# Sheet2.net
KiCad netlist of a schematic drawn in Altium Designer
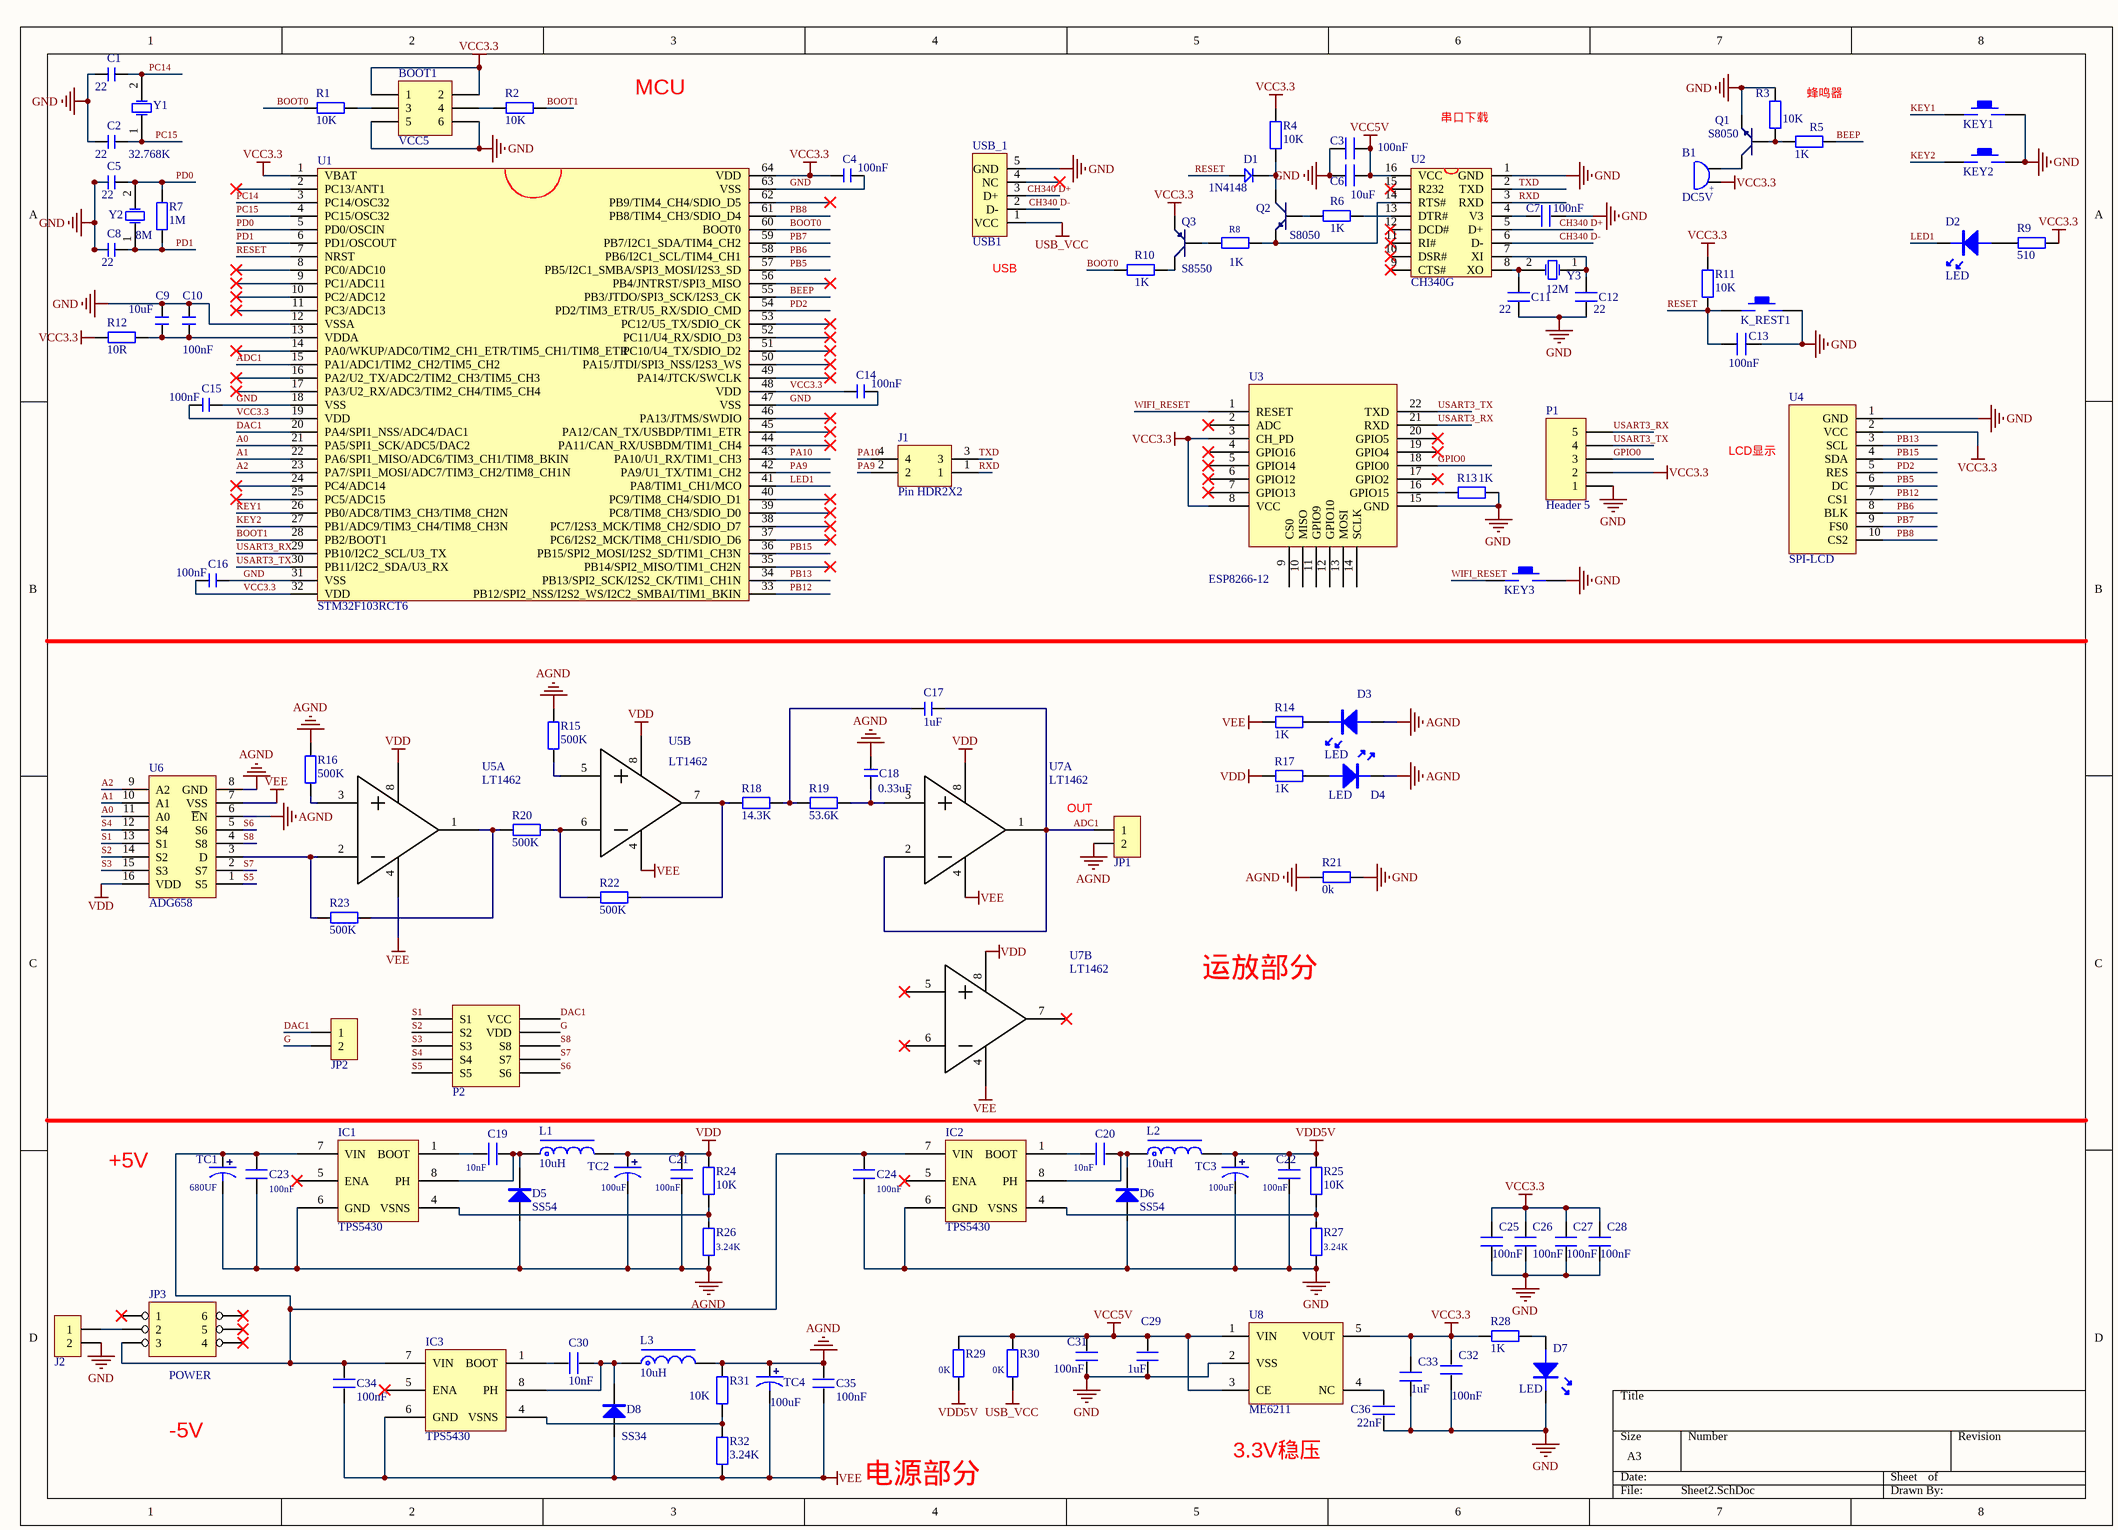
[diagram p0: Sheet2.SchDoc]

(export (version "E")
  (design (tool "Eeschema 10.0.6"))
  (components
    (comp (ref "B1")
      (value "DC5V")
      (footprint "BEEP 7.6x12x7.5")
      (description "蜂鸣器")
      (fields (field (name "版权归属") "源创客"))
      (libsource (lib "AD常用元器件集成库") (part "BEEP"))
    )
    (comp (ref "BOOT1")
      (value "VCC5")
      (footprint "HDR2X3")
      (description "Header, 3-Pin, Dual row")
      (fields (field (name "PUBLISHER") "Altium Limited"))
      (libsource (lib "SmartSensors") (part "Header 3X2"))
    )
    (comp (ref "C1")
      (value "22")
      (footprint "LC-0603_C")
      (description "无极性贴片电容")
      (fields (field (name "版权归属") "源创客"))
      (libsource (lib "SmartSensors") (part "C_1"))
    )
    (comp (ref "C2")
      (value "22")
      (footprint "LC-0603_C")
      (description "无极性贴片电容")
      (fields (field (name "版权归属") "源创客"))
      (libsource (lib "SmartSensors") (part "C_1"))
    )
    (comp (ref "C3") (value "100nF") (footprint "LC-0603_C") (libsource (lib "CORE") (part "C")))
    (comp (ref "C4")
      (value "100nF")
      (footprint "LC-0603_C")
      (description "无极性贴片电容")
      (fields (field (name "版权归属") "源创客"))
      (libsource (lib "SmartSensors") (part "C_1"))
    )
    (comp (ref "C5")
      (value "22")
      (footprint "LC-0603_C")
      (description "无极性贴片电容")
      (fields (field (name "版权归属") "源创客"))
      (libsource (lib "SmartSensors") (part "C_1"))
    )
    (comp (ref "C6") (value "10uF") (footprint "LC-0603_C") (libsource (lib "CORE") (part "C")))
    (comp (ref "C7") (value "100nF") (footprint "LC-0603_C") (libsource (lib "CORE") (part "C")))
    (comp (ref "C8")
      (value "22")
      (footprint "LC-0603_C")
      (description "无极性贴片电容")
      (fields (field (name "版权归属") "源创客"))
      (libsource (lib "SmartSensors") (part "C_1"))
    )
    (comp (ref "C9")
      (value "10uF")
      (footprint "LC-0603_C")
      (description "无极性贴片电容")
      (fields (field (name "版权归属") "源创客"))
      (libsource (lib "SmartSensors") (part "C_1"))
    )
    (comp (ref "C10")
      (value "100nF")
      (footprint "LC-0603_C")
      (description "无极性贴片电容")
      (fields (field (name "版权归属") "源创客"))
      (libsource (lib "SmartSensors") (part "C_1"))
    )
    (comp (ref "C11") (value "22") (footprint "LC-0603_C") (libsource (lib "CORE") (part "C")))
    (comp (ref "C12") (value "22") (footprint "LC-0603_C") (libsource (lib "CORE") (part "C")))
    (comp (ref "C13") (value "100nF") (footprint "LC-0603_C") (libsource (lib "CORE") (part "C")))
    (comp (ref "C14")
      (value "100nF")
      (footprint "LC-0603_C")
      (description "无极性贴片电容")
      (fields (field (name "版权归属") "源创客"))
      (libsource (lib "SmartSensors") (part "C_1"))
    )
    (comp (ref "C15")
      (value "100nF")
      (footprint "LC-0603_C")
      (description "无极性贴片电容")
      (fields (field (name "版权归属") "源创客"))
      (libsource (lib "SmartSensors") (part "C_1"))
    )
    (comp (ref "C16")
      (value "100nF")
      (footprint "LC-0603_C")
      (description "无极性贴片电容")
      (fields (field (name "版权归属") "源创客"))
      (libsource (lib "SmartSensors") (part "C_1"))
    )
    (comp (ref "C17")
      (value "1uF")
      (footprint "LC-0603_C")
      (description "无极性贴片电容")
      (fields (field (name "版权归属") "源创客"))
      (libsource (lib "AI电磁") (part "C"))
    )
    (comp (ref "C18")
      (value "0.33uF")
      (footprint "LC-0603_C")
      (description "无极性贴片电容")
      (fields (field (name "版权归属") "源创客"))
      (libsource (lib "AI电磁") (part "C"))
    )
    (comp (ref "C19") (value "10nF") (footprint "LC-0603_C") (libsource (lib "CORE") (part "C")))
    (comp (ref "C20") (value "10nF") (footprint "LC-0603_C") (libsource (lib "CORE") (part "C")))
    (comp (ref "C21") (value "100nF") (footprint "LC-0603_C") (libsource (lib "CORE") (part "C")))
    (comp (ref "C22") (value "100nF") (footprint "LC-0603_C") (libsource (lib "CORE") (part "C")))
    (comp (ref "C23") (value "100nF") (footprint "LC-0603_C") (libsource (lib "CORE") (part "C")))
    (comp (ref "C24") (value "100nF") (footprint "LC-0603_C") (libsource (lib "CORE") (part "C")))
    (comp (ref "C25") (value "100nF") (footprint "LC-0603_C") (libsource (lib "CORE") (part "C")))
    (comp (ref "C26") (value "100nF") (footprint "LC-0603_C") (libsource (lib "CORE") (part "C")))
    (comp (ref "C27") (value "100nF") (footprint "LC-0603_C") (libsource (lib "CORE") (part "C")))
    (comp (ref "C28") (value "100nF") (footprint "LC-0603_C") (libsource (lib "CORE") (part "C")))
    (comp (ref "C29") (value "1uF") (footprint "LC-0603_C") (libsource (lib "CORE") (part "C")))
    (comp (ref "C30") (value "10nF") (footprint "LC-0603_C") (libsource (lib "CORE") (part "C")))
    (comp (ref "C31") (value "100nF") (footprint "LC-0603_C") (libsource (lib "CORE") (part "C")))
    (comp (ref "C32") (value "100nF") (footprint "LC-0603_C") (libsource (lib "CORE") (part "C")))
    (comp (ref "C33") (value "1uF") (footprint "LC-0603_C") (libsource (lib "CORE") (part "C")))
    (comp (ref "C34") (value "100nF") (footprint "LC-0603_C") (libsource (lib "CORE") (part "C")))
    (comp (ref "C35") (value "100nF") (footprint "LC-0603_C") (libsource (lib "CORE") (part "C")))
    (comp (ref "C36") (value "22nF") (footprint "LC-0603_C") (libsource (lib "CORE") (part "C")))
    (comp (ref "D1") (value "1N4148") (footprint "DIODE_SOP") (libsource (lib "CORE") (part "D")))
    (comp (ref "D2") (value "LED") (footprint "LED-0805B") (libsource (lib "AI电磁") (part "LED")))
    (comp (ref "D3") (value "LED") (footprint "LED-0805B") (libsource (lib "AI电磁") (part "LED")))
    (comp (ref "D4") (value "LED") (footprint "LED-0805B") (libsource (lib "AI电磁") (part "LED")))
    (comp (ref "D5")
      (value "SS54")
      (footprint "LC-SMA(DO-214AC)_S2")
      (description "肖特基二极管")
      (fields (field (name "版权归属") "源创客"))
      (libsource (lib "AD常用元器件集成库") (part "SS54"))
    )
    (comp (ref "D6")
      (value "SS54")
      (footprint "LC-SMA(DO-214AC)_S2")
      (description "肖特基二极管")
      (fields (field (name "版权归属") "源创客"))
      (libsource (lib "AD常用元器件集成库") (part "SS54"))
    )
    (comp (ref "D7") (value "LED") (footprint "LED-0805B") (libsource (lib "AI电磁") (part "LED")))
    (comp (ref "D8")
      (value "SS34")
      (footprint "LC-SMA(DO-214AC)_S2")
      (description "肖特基二极管")
      (fields (field (name "版权归属") "源创客"))
      (libsource (lib "AD常用元器件集成库") (part "SS54"))
    )
    (comp (ref "IC1") (value "TPS5430") (footprint "SOP8") (libsource (lib "AD常用元器件集成库") (part "TPS5430")))
    (comp (ref "IC2") (value "TPS5430") (footprint "SOP8") (libsource (lib "AD常用元器件集成库") (part "TPS5430")))
    (comp (ref "IC3") (value "TPS5430") (footprint "SOP8") (libsource (lib "AD常用元器件集成库") (part "TPS5430")))
    (comp (ref "J1")
      (value "Pin HDR2X2")
      (footprint "Pin HDR2X2/2.54mm-S")
      (libsource (lib "SmartSensors") (part "Pin HDR2X2"))
    )
    (comp (ref "J2")
      (value "HDR-1X2")
      (footprint "XH2.54-2P")
      (description "2P接插件")
      (fields (field (name "版权归属") "源创客"))
      (libsource (lib "AI电磁") (part "Header 2_1"))
    )
    (comp (ref "JP1")
      (value "HDR-1X2")
      (footprint "HDR1X2")
      (description "2P接插件")
      (fields (field (name "版权归属") "源创客"))
      (libsource (lib "AI电磁") (part "Header 2"))
    )
    (comp (ref "JP2")
      (value "HDR-1X2")
      (footprint "HDR1X2")
      (description "2P接插件")
      (fields (field (name "版权归属") "源创客"))
      (libsource (lib "AI电磁") (part "Header 2"))
    )
    (comp (ref "JP3") (value "POWER") (footprint "6脚开关") (libsource (lib "AD常用元器件集成库") (part "6角开关")))
    (comp (ref "KEY1")
      (value "KEY_M")
      (footprint "DIP-6X6X5")
      (libsource (lib "SmartSensors") (part "KEY_M"))
    )
    (comp (ref "KEY2")
      (value "KEY_M")
      (footprint "DIP-6X6X5")
      (libsource (lib "SmartSensors") (part "KEY_M"))
    )
    (comp (ref "KEY3")
      (value "KEY_M")
      (footprint "SMD-3X6X2.5")
      (libsource (lib "SmartSensors") (part "KEY_M"))
    )
    (comp (ref "K_REST1")
      (value "KEY_M")
      (footprint "DIP-6X6X5")
      (libsource (lib "SmartSensors") (part "KEY_M"))
    )
    (comp (ref "L1")
      (value "10uH")
      (footprint "L-SMD-0630")
      (description "功率屏蔽电感")
      (fields (field (name "版权归属") "源创客"))
      (libsource (lib "AD常用元器件集成库") (part "L-CDRH"))
    )
    (comp (ref "L2")
      (value "10uH")
      (footprint "L-SMD-0630")
      (description "功率屏蔽电感")
      (fields (field (name "版权归属") "源创客"))
      (libsource (lib "AD常用元器件集成库") (part "L-CDRH"))
    )
    (comp (ref "L3")
      (value "10uH")
      (footprint "L-SMD-0630")
      (description "功率屏蔽电感")
      (fields (field (name "版权归属") "源创客"))
      (libsource (lib "AD常用元器件集成库") (part "L-CDRH"))
    )
    (comp (ref "P1")
      (value "Header 5")
      (footprint "HDR1X5")
      (description "Header, 5-Pin")
      (fields (field (name "PUBLISHER") "Altium Limited"))
      (libsource (lib "SmartSensors") (part "Header 5"))
    )
    (comp (ref "P2") (value "senor") (footprint "sensor-con pin 10") (libsource (lib "AI电磁") (part "senor")))
    (comp (ref "Q1")
      (value "S8050")
      (footprint "SOT-23R")
      (description "8050/BCW846/BCW847")
      (libsource (lib "CORE") (part "NPN"))
    )
    (comp (ref "Q2")
      (value "S8050")
      (footprint "SOT-23R")
      (description "8050/BCW846/BCW847")
      (libsource (lib "CORE") (part "NPN"))
    )
    (comp (ref "Q3")
      (value "S8550")
      (footprint "SOT-23R")
      (description "8550/BCW68")
      (libsource (lib "CORE") (part "PNP"))
    )
    (comp (ref "R1")
      (value "10K")
      (footprint "R 0603_M")
      (description "贴片电阻")
      (fields (field (name "版权归属") "源创客"))
      (libsource (lib "SmartSensors") (part "R"))
    )
    (comp (ref "R2")
      (value "10K")
      (footprint "R 0603_M")
      (description "贴片电阻")
      (fields (field (name "版权归属") "源创客"))
      (libsource (lib "SmartSensors") (part "R"))
    )
    (comp (ref "R3")
      (value "10K")
      (footprint "R 0603_M")
      (description "贴片电阻")
      (fields (field (name "版权归属") "源创客"))
      (libsource (lib "AD常用元器件集成库") (part "R"))
    )
    (comp (ref "R4")
      (value "10K")
      (footprint "R 0603_M")
      (description "贴片电阻")
      (fields (field (name "版权归属") "源创客"))
      (libsource (lib "AD常用元器件集成库") (part "R"))
    )
    (comp (ref "R5")
      (value "1K")
      (footprint "R 0603_M")
      (description "贴片电阻")
      (fields (field (name "版权归属") "源创客"))
      (libsource (lib "AD常用元器件集成库") (part "R"))
    )
    (comp (ref "R6")
      (value "1K")
      (footprint "R 0603_M")
      (description "贴片电阻")
      (fields (field (name "版权归属") "源创客"))
      (libsource (lib "AD常用元器件集成库") (part "R"))
    )
    (comp (ref "R7")
      (value "1M")
      (footprint "R 0603_M")
      (description "贴片电阻")
      (fields (field (name "版权归属") "源创客"))
      (libsource (lib "SmartSensors") (part "R"))
    )
    (comp (ref "R8")
      (value "1K")
      (footprint "R 0603_M")
      (description "贴片电阻")
      (fields (field (name "版权归属") "源创客"))
      (libsource (lib "AD常用元器件集成库") (part "R"))
    )
    (comp (ref "R9")
      (value "510")
      (footprint "R 0603_M")
      (description "贴片电阻")
      (fields (field (name "版权归属") "源创客"))
      (libsource (lib "AD常用元器件集成库") (part "R"))
    )
    (comp (ref "R10")
      (value "1K")
      (footprint "R 0603_M")
      (description "贴片电阻")
      (fields (field (name "版权归属") "源创客"))
      (libsource (lib "AD常用元器件集成库") (part "R"))
    )
    (comp (ref "R11")
      (value "10K")
      (footprint "R 0603_M")
      (description "贴片电阻")
      (fields (field (name "版权归属") "源创客"))
      (libsource (lib "AD常用元器件集成库") (part "R"))
    )
    (comp (ref "R12")
      (value "10R")
      (footprint "R 0603_M")
      (description "贴片电阻")
      (fields (field (name "版权归属") "源创客"))
      (libsource (lib "SmartSensors") (part "R"))
    )
    (comp (ref "R13")
      (value "1K")
      (footprint "R 0603_M")
      (description "贴片电阻")
      (fields (field (name "版权归属") "源创客"))
      (libsource (lib "AI电磁") (part "R"))
    )
    (comp (ref "R14")
      (value "1K")
      (footprint "R 0603_M")
      (description "贴片电阻")
      (fields (field (name "版权归属") "源创客"))
      (libsource (lib "AI电磁") (part "R"))
    )
    (comp (ref "R15")
      (value "500K")
      (footprint "R 0603_M")
      (description "贴片电阻")
      (fields (field (name "版权归属") "源创客"))
      (libsource (lib "AI电磁") (part "R"))
    )
    (comp (ref "R16")
      (value "500K")
      (footprint "R 0603_M")
      (description "贴片电阻")
      (fields (field (name "版权归属") "源创客"))
      (libsource (lib "AI电磁") (part "R"))
    )
    (comp (ref "R17")
      (value "1K")
      (footprint "R 0603_M")
      (description "贴片电阻")
      (fields (field (name "版权归属") "源创客"))
      (libsource (lib "AI电磁") (part "R"))
    )
    (comp (ref "R18")
      (value "14.3K")
      (footprint "R 0603_M")
      (description "贴片电阻")
      (fields (field (name "版权归属") "源创客"))
      (libsource (lib "AI电磁") (part "R"))
    )
    (comp (ref "R19")
      (value "53.6K")
      (footprint "R 0603_M")
      (description "贴片电阻")
      (fields (field (name "版权归属") "源创客"))
      (libsource (lib "AI电磁") (part "R"))
    )
    (comp (ref "R20")
      (value "500K")
      (footprint "R 0603_M")
      (description "贴片电阻")
      (fields (field (name "版权归属") "源创客"))
      (libsource (lib "AI电磁") (part "R"))
    )
    (comp (ref "R21")
      (value "0k")
      (footprint "R 0603_M")
      (description "贴片电阻")
      (fields (field (name "版权归属") "源创客"))
      (libsource (lib "AI电磁") (part "R"))
    )
    (comp (ref "R22")
      (value "500K")
      (footprint "R 0603_M")
      (description "贴片电阻")
      (fields (field (name "版权归属") "源创客"))
      (libsource (lib "AI电磁") (part "R"))
    )
    (comp (ref "R23")
      (value "500K")
      (footprint "R 0603_M")
      (description "贴片电阻")
      (fields (field (name "版权归属") "源创客"))
      (libsource (lib "AI电磁") (part "R"))
    )
    (comp (ref "R24")
      (value "10K")
      (footprint "R 0603_M")
      (description "贴片电阻")
      (fields (field (name "版权归属") "源创客"))
      (libsource (lib "AI电磁") (part "R"))
    )
    (comp (ref "R25")
      (value "10K")
      (footprint "R 0603_M")
      (description "贴片电阻")
      (fields (field (name "版权归属") "源创客"))
      (libsource (lib "AI电磁") (part "R"))
    )
    (comp (ref "R26")
      (value "3.24K")
      (footprint "R 0603_M")
      (description "贴片电阻")
      (fields (field (name "版权归属") "源创客"))
      (libsource (lib "AI电磁") (part "R"))
    )
    (comp (ref "R27")
      (value "3.24K")
      (footprint "R 0603_M")
      (description "贴片电阻")
      (fields (field (name "版权归属") "源创客"))
      (libsource (lib "AI电磁") (part "R"))
    )
    (comp (ref "R28")
      (value "1K")
      (footprint "R 0603_M")
      (description "贴片电阻")
      (fields (field (name "版权归属") "源创客"))
      (libsource (lib "AI电磁") (part "R"))
    )
    (comp (ref "R29")
      (value "0K")
      (footprint "R 0603_M")
      (description "贴片电阻")
      (fields (field (name "版权归属") "源创客"))
      (libsource (lib "AI电磁") (part "R"))
    )
    (comp (ref "R30")
      (value "0K")
      (footprint "R 0603_M")
      (description "贴片电阻")
      (fields (field (name "版权归属") "源创客"))
      (libsource (lib "AI电磁") (part "R"))
    )
    (comp (ref "R31")
      (value "10K")
      (footprint "R 0603_M")
      (description "贴片电阻")
      (fields (field (name "版权归属") "源创客"))
      (libsource (lib "AI电磁") (part "R"))
    )
    (comp (ref "R32")
      (value "3.24K")
      (footprint "R 0603_M")
      (description "贴片电阻")
      (fields (field (name "版权归属") "源创客"))
      (libsource (lib "AI电磁") (part "R"))
    )
    (comp (ref "TC1")
      (value "680UF")
      (footprint "SMD-EC6.3X6.3X10")
      (description "钽电容")
      (libsource (lib "AD常用元器件集成库") (part "TCAP_1"))
    )
    (comp (ref "TC2")
      (value "100uF")
      (footprint "TAJ-A/3216")
      (description "钽电容")
      (libsource (lib "AD常用元器件集成库") (part "TCAP_1"))
    )
    (comp (ref "TC3")
      (value "100uF")
      (footprint "TAJ-A/3216")
      (description "钽电容")
      (libsource (lib "AD常用元器件集成库") (part "TCAP_1"))
    )
    (comp (ref "TC4")
      (value "100uF")
      (footprint "TAJ-A/3216")
      (description "钽电容")
      (libsource (lib "AD常用元器件集成库") (part "TCAP_1"))
    )
    (comp (ref "U1")
      (value "STM32F103RCT6")
      (footprint "LQFP64")
      (libsource (lib "SmartSensors") (part "STM32F103RDT6"))
    )
    (comp (ref "U2")
      (value "CH340G")
      (footprint "SOP16M")
      (description "USB2UART")
      (libsource (lib "CORE") (part "CH340G"))
    )
    (comp (ref "U3")
      (value "ESP8266-12")
      (footprint "ESP8266-12")
      (libsource (lib "SmartSensors") (part "ESP8266-12"))
    )
    (comp (ref "U4")
      (value "SPI-LCD")
      (footprint "Fe-HDR1X10/2.54-S")
      (libsource (lib "SmartSensors") (part "SPI-LCD"))
    )
    (comp (ref "U5") (value "LT1462") (footprint "SOP8") (libsource (lib "AI电磁") (part "LT1462_1")))
    (comp (ref "U6") (value "ADG658") (footprint "ADG658-SOP-16") (libsource (lib "AI电磁") (part "ADG658")))
    (comp (ref "U7") (value "LT1462") (footprint "SOP8") (libsource (lib "AI电磁") (part "LT1462_1")))
    (comp (ref "U8") (value "ME6211") (footprint "SOT23-5") (libsource (lib "AD常用元器件集成库") (part "ME6211")))
    (comp (ref "USB_1") (value "USB1") (footprint "USB-micro_B") (libsource (lib "CORE") (part "USB5")))
    (comp (ref "Y1")
      (value "32.768K")
      (footprint "OSC 3215-2P")
      (description "Crystal Oscillator")
      (fields (field (name "PUBLISHER") "Altium Limited"))
      (libsource (lib "SmartSensors") (part "XTAL_2"))
    )
    (comp (ref "Y2")
      (value "8M")
      (footprint "OSC 5032-2P")
      (description "Crystal Oscillator")
      (fields (field (name "PUBLISHER") "Altium Limited"))
      (libsource (lib "SmartSensors") (part "XTAL_2"))
    )
    (comp (ref "Y3")
      (value "12M")
      (footprint "OSC 5032-2P")
      (description "Crystal Oscillator")
      (fields (field (name "PUBLISHER") "Altium Limited"))
      (libsource (lib "LD3320语音助手PCB_Project1") (part "XTAL_2"))
    )
  )
  (nets
    (net (code "1") (name "/A0") (class "Default")
      (node (ref "U1") (pin "21") (pinfunction "PA5/SPI1_SCK/ADC5/DAC2_21") (pintype "passive"))
      (node (ref "U6") (pin "11") (pinfunction "A0_11") (pintype "passive"))
    )
    (net (code "2") (name "/A1") (class "Default")
      (node (ref "U1") (pin "22") (pinfunction "PA6/SPI1_MISO/ADC6/TIM3_CH1/TIM8_BKIN_22") (pintype "passive"))
      (node (ref "U6") (pin "10") (pinfunction "A1_10") (pintype "passive"))
    )
    (net (code "3") (name "/A2") (class "Default")
      (node (ref "U1") (pin "23") (pinfunction "PA7/SPI1_MOSI/ADC7/TIM3_CH2/TIM8_CH1N_23") (pintype "passive"))
      (node (ref "U6") (pin "9") (pinfunction "A2_9") (pintype "passive"))
    )
    (net (code "4") (name "/ADC1") (class "Default")
      (node (ref "C17") (pin "2") (pinfunction "2_2") (pintype "passive"))
      (node (ref "JP1") (pin "1") (pinfunction "1_1") (pintype "passive"))
      (node (ref "U1") (pin "15") (pinfunction "PA1/ADC1/TIM2_CH2/TIM5_CH2_15") (pintype "passive"))
      (node (ref "U7") (pin "1") (pinfunction "out_1") (pintype "passive"))
      (node (ref "U7") (pin "2") (pinfunction "-_2") (pintype "passive"))
    )
    (net (code "5") (name "/BEEP") (class "Default")
      (node (ref "R5") (pin "2") (pinfunction "2_2") (pintype "passive"))
      (node (ref "U1") (pin "55") (pinfunction "PB3/JTDO/SPI3_SCK/I2S3_CK_55") (pintype "passive"))
    )
    (net (code "6") (name "/BOOT0") (class "Default")
      (node (ref "R1") (pin "1") (pinfunction "1_1") (pintype "passive"))
      (node (ref "R10") (pin "2") (pinfunction "2_2") (pintype "passive"))
      (node (ref "U1") (pin "60") (pinfunction "BOOT0_60") (pintype "passive"))
    )
    (net (code "7") (name "/BOOT1") (class "Default")
      (node (ref "R2") (pin "2") (pinfunction "2_2") (pintype "passive"))
      (node (ref "U1") (pin "28") (pinfunction "PB2/BOOT1_28") (pintype "passive"))
    )
    (net (code "8") (name "/CH340 D+") (class "Default")
      (node (ref "U2") (pin "5") (pinfunction "D+_5") (pintype "passive"))
      (node (ref "USB_1") (pin "3") (pinfunction "D+_3") (pintype "passive"))
    )
    (net (code "9") (name "/CH340 D-") (class "Default")
      (node (ref "U2") (pin "6") (pinfunction "D-_6") (pintype "passive"))
      (node (ref "USB_1") (pin "2") (pinfunction "D-_2") (pintype "passive"))
    )
    (net (code "10") (name "/DAC1") (class "Default")
      (node (ref "JP2") (pin "1") (pinfunction "1_1") (pintype "passive"))
      (node (ref "P2") (pin "10") (pinfunction "VCC_10") (pintype "passive"))
      (node (ref "U1") (pin "20") (pinfunction "PA4/SPI1_NSS/ADC4/DAC1_20") (pintype "passive"))
    )
    (net (code "11") (name "/G") (class "Default")
      (node (ref "JP2") (pin "2") (pinfunction "2_2") (pintype "passive"))
      (node (ref "P2") (pin "9") (pinfunction "VDD_9") (pintype "passive"))
    )
    (net (code "12") (name "/GPIO0") (class "Default")
      (node (ref "P1") (pin "3") (pinfunction "3_3") (pintype "passive"))
      (node (ref "U3") (pin "18") (pinfunction "GPIO0_18") (pintype "passive"))
    )
    (net (code "13") (name "/KEY1") (class "Default")
      (node (ref "KEY1") (pin "1") (pinfunction "1_1") (pintype "passive"))
      (node (ref "U1") (pin "26") (pinfunction "PB0/ADC8/TIM3_CH3/TIM8_CH2N_26") (pintype "passive"))
    )
    (net (code "14") (name "/KEY2") (class "Default")
      (node (ref "KEY2") (pin "1") (pinfunction "1_1") (pintype "passive"))
      (node (ref "U1") (pin "27") (pinfunction "PB1/ADC9/TIM3_CH4/TIM8_CH3N_27") (pintype "passive"))
    )
    (net (code "15") (name "/LED1") (class "Default")
      (node (ref "D2") (pin "K") (pinfunction "K_K") (pintype "passive"))
      (node (ref "U1") (pin "41") (pinfunction "PA8/TIM1_CH1/MCO_41") (pintype "passive"))
    )
    (net (code "16") (name "/PA9") (class "Default")
      (node (ref "J1") (pin "2") (pinfunction "2_2") (pintype "passive"))
      (node (ref "U1") (pin "42") (pinfunction "PA9/U1_TX/TIM1_CH2_42") (pintype "passive"))
    )
    (net (code "17") (name "/PA10") (class "Default")
      (node (ref "J1") (pin "4") (pinfunction "4_4") (pintype "passive"))
      (node (ref "U1") (pin "43") (pinfunction "PA10/U1_RX/TIM1_CH3_43") (pintype "passive"))
    )
    (net (code "18") (name "/PB5") (class "Default")
      (node (ref "U1") (pin "57") (pinfunction "PB5/I2C1_SMBA/SPI3_MOSI/I2S3_SD_57") (pintype "passive"))
      (node (ref "U4") (pin "6") (pinfunction "DC_6") (pintype "passive"))
    )
    (net (code "19") (name "/PB6") (class "Default")
      (node (ref "U1") (pin "58") (pinfunction "PB6/I2C1_SCL/TIM4_CH1_58") (pintype "passive"))
      (node (ref "U4") (pin "8") (pinfunction "BLK_8") (pintype "passive"))
    )
    (net (code "20") (name "/PB7") (class "Default")
      (node (ref "U1") (pin "59") (pinfunction "PB7/I2C1_SDA/TIM4_CH2_59") (pintype "passive"))
      (node (ref "U4") (pin "9") (pinfunction "FS0_9") (pintype "passive"))
    )
    (net (code "21") (name "/PB8") (class "Default")
      (node (ref "U1") (pin "61") (pinfunction "PB8/TIM4_CH3/SDIO_D4_61") (pintype "passive"))
      (node (ref "U4") (pin "10") (pinfunction "CS2_10") (pintype "passive"))
    )
    (net (code "22") (name "/PB12") (class "Default")
      (node (ref "U1") (pin "33") (pinfunction "PB12/SPI2_NSS/I2S2_WS/I2C2_SMBAI/TIM1_BKIN_33") (pintype "passive"))
      (node (ref "U4") (pin "7") (pinfunction "CS1_7") (pintype "passive"))
    )
    (net (code "23") (name "/PB13") (class "Default")
      (node (ref "U1") (pin "34") (pinfunction "PB13/SPI2_SCK/I2S2_CK/TIM1_CH1N_34") (pintype "passive"))
      (node (ref "U4") (pin "3") (pinfunction "SCL_3") (pintype "passive"))
    )
    (net (code "24") (name "/PB15") (class "Default")
      (node (ref "U1") (pin "36") (pinfunction "PB15/SPI2_MOSI/I2S2_SD/TIM1_CH3N_36") (pintype "passive"))
      (node (ref "U4") (pin "4") (pinfunction "SDA_4") (pintype "passive"))
    )
    (net (code "25") (name "/PC14") (class "Default")
      (node (ref "C1") (pin "2") (pinfunction "2_2") (pintype "passive"))
      (node (ref "U1") (pin "3") (pinfunction "PC14/OSC32_3") (pintype "passive"))
      (node (ref "Y1") (pin "2") (pinfunction "OSC2_2") (pintype "passive"))
    )
    (net (code "26") (name "/PC15") (class "Default")
      (node (ref "C2") (pin "2") (pinfunction "2_2") (pintype "passive"))
      (node (ref "U1") (pin "4") (pinfunction "PC15/OSC32_4") (pintype "passive"))
      (node (ref "Y1") (pin "1") (pinfunction "OSC1_1") (pintype "passive"))
    )
    (net (code "27") (name "/PD0") (class "Default")
      (node (ref "C5") (pin "2") (pinfunction "2_2") (pintype "passive"))
      (node (ref "R7") (pin "2") (pinfunction "2_2") (pintype "passive"))
      (node (ref "U1") (pin "5") (pinfunction "PD0/OSCIN_5") (pintype "passive"))
      (node (ref "Y2") (pin "2") (pinfunction "OSC2_2") (pintype "passive"))
    )
    (net (code "28") (name "/PD1") (class "Default")
      (node (ref "C8") (pin "2") (pinfunction "2_2") (pintype "passive"))
      (node (ref "R7") (pin "1") (pinfunction "1_1") (pintype "passive"))
      (node (ref "U1") (pin "6") (pinfunction "PD1/OSCOUT_6") (pintype "passive"))
      (node (ref "Y2") (pin "1") (pinfunction "OSC1_1") (pintype "passive"))
    )
    (net (code "29") (name "/PD2") (class "Default")
      (node (ref "U1") (pin "54") (pinfunction "PD2/TIM3_ETR/U5_RX/SDIO_CMD_54") (pintype "passive"))
      (node (ref "U4") (pin "5") (pinfunction "RES_5") (pintype "passive"))
    )
    (net (code "30") (name "/RESET") (class "Default")
      (node (ref "C13") (pin "2") (pintype "passive"))
      (node (ref "D1") (pin "1") (pintype "passive"))
      (node (ref "K_REST1") (pin "1") (pinfunction "1_1") (pintype "passive"))
      (node (ref "R11") (pin "1") (pinfunction "1_1") (pintype "passive"))
      (node (ref "U1") (pin "7") (pinfunction "NRST_7") (pintype "passive"))
    )
    (net (code "31") (name "/RXD") (class "Default")
      (node (ref "J1") (pin "1") (pinfunction "1_1") (pintype "passive"))
      (node (ref "U2") (pin "3") (pinfunction "RXD_3") (pintype "passive"))
    )
    (net (code "32") (name "/S1") (class "Default")
      (node (ref "P2") (pin "1") (pinfunction "S1_1") (pintype "passive"))
      (node (ref "U6") (pin "13") (pinfunction "S1_13") (pintype "passive"))
    )
    (net (code "33") (name "/S2") (class "Default")
      (node (ref "P2") (pin "2") (pinfunction "S2_2") (pintype "passive"))
      (node (ref "U6") (pin "14") (pinfunction "S2_14") (pintype "passive"))
    )
    (net (code "34") (name "/S3") (class "Default")
      (node (ref "P2") (pin "3") (pinfunction "S3_3") (pintype "passive"))
      (node (ref "U6") (pin "15") (pinfunction "S3_15") (pintype "passive"))
    )
    (net (code "35") (name "/S4") (class "Default")
      (node (ref "P2") (pin "4") (pinfunction "S4_4") (pintype "passive"))
      (node (ref "U6") (pin "12") (pinfunction "S4_12") (pintype "passive"))
    )
    (net (code "36") (name "/S5") (class "Default")
      (node (ref "P2") (pin "5") (pinfunction "S5_5") (pintype "passive"))
      (node (ref "U6") (pin "1") (pinfunction "S5_1") (pintype "passive"))
    )
    (net (code "37") (name "/S6") (class "Default")
      (node (ref "P2") (pin "6") (pinfunction "S6_6") (pintype "passive"))
      (node (ref "U6") (pin "5") (pinfunction "S6_5") (pintype "passive"))
    )
    (net (code "38") (name "/S7") (class "Default")
      (node (ref "P2") (pin "7") (pinfunction "S7_7") (pintype "passive"))
      (node (ref "U6") (pin "2") (pinfunction "S7_2") (pintype "passive"))
    )
    (net (code "39") (name "/S8") (class "Default")
      (node (ref "P2") (pin "8") (pinfunction "S8_8") (pintype "passive"))
      (node (ref "U6") (pin "4") (pinfunction "S8_4") (pintype "passive"))
    )
    (net (code "40") (name "/TXD") (class "Default")
      (node (ref "J1") (pin "3") (pinfunction "3_3") (pintype "passive"))
      (node (ref "U2") (pin "2") (pinfunction "TXD_2") (pintype "passive"))
    )
    (net (code "41") (name "/USART3_RX") (class "Default")
      (node (ref "P1") (pin "5") (pinfunction "5_5") (pintype "passive"))
      (node (ref "U1") (pin "29") (pinfunction "PB10/I2C2_SCL/U3_TX_29") (pintype "passive"))
      (node (ref "U3") (pin "21") (pinfunction "RXD_21") (pintype "passive"))
    )
    (net (code "42") (name "/USART3_TX") (class "Default")
      (node (ref "P1") (pin "4") (pinfunction "4_4") (pintype "passive"))
      (node (ref "U1") (pin "30") (pinfunction "PB11/I2C2_SDA/U3_RX_30") (pintype "passive"))
      (node (ref "U3") (pin "22") (pinfunction "TXD_22") (pintype "passive"))
    )
    (net (code "43") (name "/WIFI_RESET") (class "Default")
      (node (ref "KEY3") (pin "1") (pinfunction "1_1") (pintype "passive"))
      (node (ref "U3") (pin "1") (pinfunction "RESET_1") (pintype "passive"))
    )
    (net (code "44") (name "AGND") (class "Default")
      (node (ref "C18") (pin "1") (pinfunction "1_1") (pintype "passive"))
      (node (ref "C21") (pin "2") (pintype "passive"))
      (node (ref "C23") (pin "1") (pintype "passive"))
      (node (ref "C35") (pin "1") (pintype "passive"))
      (node (ref "D3") (pin "A") (pinfunction "A_A") (pintype "passive"))
      (node (ref "D4") (pin "K") (pinfunction "K_K") (pintype "passive"))
      (node (ref "D5") (pin "1") (pinfunction "A_1") (pintype "passive"))
      (node (ref "IC1") (pin "6") (pinfunction "GND_6") (pintype "passive"))
      (node (ref "JP1") (pin "2") (pinfunction "2_2") (pintype "passive"))
      (node (ref "L3") (pin "2") (pinfunction "2_2") (pintype "passive"))
      (node (ref "R15") (pin "1") (pinfunction "1_1") (pintype "passive"))
      (node (ref "R16") (pin "1") (pinfunction "1_1") (pintype "passive"))
      (node (ref "R21") (pin "2") (pinfunction "2_2") (pintype "passive"))
      (node (ref "R26") (pin "1") (pinfunction "1_1") (pintype "passive"))
      (node (ref "R31") (pin "2") (pinfunction "2_2") (pintype "passive"))
      (node (ref "TC1") (pin "2") (pinfunction "2_2") (pintype "passive"))
      (node (ref "TC2") (pin "2") (pinfunction "2_2") (pintype "passive"))
      (node (ref "TC4") (pin "1") (pinfunction "1_1") (pintype "passive"))
      (node (ref "U6") (pin "6") (pinfunction "~{E}N_6") (pintype "passive"))
      (node (ref "U6") (pin "8") (pinfunction "GND_8") (pintype "passive"))
    )
    (net (code "45") (name "GND") (class "Default")
      (node (ref "BOOT1") (pin "5") (pinfunction "5_5") (pintype "passive"))
      (node (ref "BOOT1") (pin "6") (pinfunction "6_6") (pintype "passive"))
      (node (ref "C1") (pin "1") (pinfunction "1_1") (pintype "passive"))
      (node (ref "C10") (pin "2") (pinfunction "2_2") (pintype "passive"))
      (node (ref "C11") (pin "1") (pintype "passive"))
      (node (ref "C12") (pin "1") (pintype "passive"))
      (node (ref "C13") (pin "1") (pintype "passive"))
      (node (ref "C14") (pin "1") (pinfunction "1_1") (pintype "passive"))
      (node (ref "C15") (pin "1") (pinfunction "1_1") (pintype "passive"))
      (node (ref "C16") (pin "1") (pinfunction "1_1") (pintype "passive"))
      (node (ref "C2") (pin "1") (pinfunction "1_1") (pintype "passive"))
      (node (ref "C22") (pin "2") (pintype "passive"))
      (node (ref "C24") (pin "1") (pintype "passive"))
      (node (ref "C25") (pin "2") (pintype "passive"))
      (node (ref "C26") (pin "2") (pintype "passive"))
      (node (ref "C27") (pin "2") (pintype "passive"))
      (node (ref "C28") (pin "2") (pintype "passive"))
      (node (ref "C29") (pin "2") (pintype "passive"))
      (node (ref "C3") (pin "1") (pintype "passive"))
      (node (ref "C31") (pin "2") (pintype "passive"))
      (node (ref "C32") (pin "2") (pintype "passive"))
      (node (ref "C33") (pin "2") (pintype "passive"))
      (node (ref "C36") (pin "2") (pintype "passive"))
      (node (ref "C4") (pin "1") (pinfunction "1_1") (pintype "passive"))
      (node (ref "C5") (pin "1") (pinfunction "1_1") (pintype "passive"))
      (node (ref "C6") (pin "1") (pintype "passive"))
      (node (ref "C7") (pin "2") (pintype "passive"))
      (node (ref "C8") (pin "1") (pinfunction "1_1") (pintype "passive"))
      (node (ref "C9") (pin "2") (pinfunction "2_2") (pintype "passive"))
      (node (ref "D6") (pin "1") (pinfunction "A_1") (pintype "passive"))
      (node (ref "D7") (pin "K") (pinfunction "K_K") (pintype "passive"))
      (node (ref "IC2") (pin "6") (pinfunction "GND_6") (pintype "passive"))
      (node (ref "J2") (pin "2") (pinfunction "2_2") (pintype "passive"))
      (node (ref "KEY1") (pin "2") (pinfunction "2_2") (pintype "passive"))
      (node (ref "KEY2") (pin "2") (pinfunction "2_2") (pintype "passive"))
      (node (ref "KEY3") (pin "2") (pinfunction "2_2") (pintype "passive"))
      (node (ref "K_REST1") (pin "2") (pinfunction "2_2") (pintype "passive"))
      (node (ref "P1") (pin "1") (pinfunction "1_1") (pintype "passive"))
      (node (ref "Q1") (pin "1") (pinfunction "E_1") (pintype "passive"))
      (node (ref "R13") (pin "1") (pinfunction "1_1") (pintype "passive"))
      (node (ref "R21") (pin "1") (pinfunction "1_1") (pintype "passive"))
      (node (ref "R27") (pin "1") (pinfunction "1_1") (pintype "passive"))
      (node (ref "R3") (pin "1") (pinfunction "1_1") (pintype "passive"))
      (node (ref "TC3") (pin "2") (pinfunction "2_2") (pintype "passive"))
      (node (ref "U1") (pin "12") (pinfunction "VSSA_12") (pintype "passive"))
      (node (ref "U1") (pin "18") (pinfunction "VSS_18") (pintype "passive"))
      (node (ref "U1") (pin "31") (pinfunction "VSS_31") (pintype "passive"))
      (node (ref "U1") (pin "47") (pinfunction "VSS_47") (pintype "passive"))
      (node (ref "U1") (pin "63") (pinfunction "VSS_63") (pintype "passive"))
      (node (ref "U2") (pin "1") (pinfunction "GND_1") (pintype "passive"))
      (node (ref "U3") (pin "15") (pinfunction "GND_15") (pintype "passive"))
      (node (ref "U4") (pin "1") (pinfunction "GND_1") (pintype "passive"))
      (node (ref "U8") (pin "2") (pinfunction "VSS_2") (pintype "passive"))
      (node (ref "USB_1") (pin "5") (pinfunction "GND_5") (pintype "passive"))
    )
    (net (code "46") (name "Net-(BOOT1-Pad3)") (class "Default")
      (node (ref "BOOT1") (pin "3") (pinfunction "3_3") (pintype "passive"))
      (node (ref "R1") (pin "2") (pinfunction "2_2") (pintype "passive"))
    )
    (net (code "47") (name "Net-(BOOT1-Pad4)") (class "Default")
      (node (ref "BOOT1") (pin "4") (pinfunction "4_4") (pintype "passive"))
      (node (ref "R2") (pin "1") (pinfunction "1_1") (pintype "passive"))
    )
    (net (code "48") (name "Net-(C17-Pad1)") (class "Default")
      (node (ref "C17") (pin "1") (pinfunction "1_1") (pintype "passive"))
      (node (ref "R18") (pin "2") (pinfunction "2_2") (pintype "passive"))
      (node (ref "R19") (pin "1") (pinfunction "1_1") (pintype "passive"))
    )
    (net (code "49") (name "Net-(D2-PadA)") (class "Default")
      (node (ref "D2") (pin "A") (pinfunction "A_A") (pintype "passive"))
      (node (ref "R9") (pin "2") (pinfunction "2_2") (pintype "passive"))
    )
    (net (code "50") (name "Net-(D3-PadK)") (class "Default")
      (node (ref "D3") (pin "K") (pinfunction "K_K") (pintype "passive"))
      (node (ref "R14") (pin "1") (pinfunction "1_1") (pintype "passive"))
    )
    (net (code "51") (name "Net-(D4-PadA)") (class "Default")
      (node (ref "D4") (pin "A") (pinfunction "A_A") (pintype "passive"))
      (node (ref "R17") (pin "1") (pinfunction "1_1") (pintype "passive"))
    )
    (net (code "52") (name "Net-(D5-K)") (class "Default")
      (node (ref "C19") (pin "1") (pintype "passive"))
      (node (ref "D5") (pin "2") (pinfunction "K_2") (pintype "passive"))
      (node (ref "IC1") (pin "8") (pinfunction "PH_8") (pintype "passive"))
      (node (ref "L1") (pin "1") (pinfunction "1_1") (pintype "passive"))
    )
    (net (code "53") (name "Net-(D6-K)") (class "Default")
      (node (ref "C20") (pin "1") (pintype "passive"))
      (node (ref "D6") (pin "2") (pinfunction "K_2") (pintype "passive"))
      (node (ref "IC2") (pin "8") (pinfunction "PH_8") (pintype "passive"))
      (node (ref "L2") (pin "1") (pinfunction "1_1") (pintype "passive"))
    )
    (net (code "54") (name "Net-(D7-PadA)") (class "Default")
      (node (ref "D7") (pin "A") (pinfunction "A_A") (pintype "passive"))
      (node (ref "R28") (pin "1") (pinfunction "1_1") (pintype "passive"))
    )
    (net (code "55") (name "Net-(D8-K)") (class "Default")
      (node (ref "C30") (pin "1") (pintype "passive"))
      (node (ref "D8") (pin "2") (pinfunction "K_2") (pintype "passive"))
      (node (ref "IC3") (pin "8") (pinfunction "PH_8") (pintype "passive"))
      (node (ref "L3") (pin "1") (pinfunction "1_1") (pintype "passive"))
    )
    (net (code "56") (name "Net-(IC1-BOOT)") (class "Default")
      (node (ref "C19") (pin "2") (pintype "passive"))
      (node (ref "IC1") (pin "1") (pinfunction "BOOT_1") (pintype "passive"))
    )
    (net (code "57") (name "Net-(IC1-VIN)") (class "Default")
      (node (ref "C23") (pin "2") (pintype "passive"))
      (node (ref "C24") (pin "2") (pintype "passive"))
      (node (ref "C34") (pin "2") (pintype "passive"))
      (node (ref "IC1") (pin "7") (pinfunction "VIN_7") (pintype "passive"))
      (node (ref "IC2") (pin "7") (pinfunction "VIN_7") (pintype "passive"))
      (node (ref "IC3") (pin "7") (pinfunction "VIN_7") (pintype "passive"))
      (node (ref "JP3") (pin "3") (pinfunction "3_3") (pintype "passive"))
      (node (ref "TC1") (pin "1") (pinfunction "1_1") (pintype "passive"))
    )
    (net (code "58") (name "Net-(IC1-VSNS)") (class "Default")
      (node (ref "IC1") (pin "4") (pinfunction "VSNS_4") (pintype "passive"))
      (node (ref "R24") (pin "1") (pinfunction "1_1") (pintype "passive"))
      (node (ref "R26") (pin "2") (pinfunction "2_2") (pintype "passive"))
    )
    (net (code "59") (name "Net-(IC2-BOOT)") (class "Default")
      (node (ref "C20") (pin "2") (pintype "passive"))
      (node (ref "IC2") (pin "1") (pinfunction "BOOT_1") (pintype "passive"))
    )
    (net (code "60") (name "Net-(IC2-VSNS)") (class "Default")
      (node (ref "IC2") (pin "4") (pinfunction "VSNS_4") (pintype "passive"))
      (node (ref "R25") (pin "1") (pinfunction "1_1") (pintype "passive"))
      (node (ref "R27") (pin "2") (pinfunction "2_2") (pintype "passive"))
    )
    (net (code "61") (name "Net-(IC3-BOOT)") (class "Default")
      (node (ref "C30") (pin "2") (pintype "passive"))
      (node (ref "IC3") (pin "1") (pinfunction "BOOT_1") (pintype "passive"))
    )
    (net (code "62") (name "Net-(IC3-VSNS)") (class "Default")
      (node (ref "IC3") (pin "4") (pinfunction "VSNS_4") (pintype "passive"))
      (node (ref "R31") (pin "1") (pinfunction "1_1") (pintype "passive"))
      (node (ref "R32") (pin "2") (pinfunction "2_2") (pintype "passive"))
    )
    (net (code "63") (name "Net-(J2-Pad1)") (class "Default")
      (node (ref "J2") (pin "1") (pinfunction "1_1") (pintype "passive"))
      (node (ref "JP3") (pin "2") (pinfunction "2_2") (pintype "passive"))
    )
    (net (code "64") (name "Net-(Q1-B)") (class "Default")
      (node (ref "Q1") (pin "2") (pinfunction "B_2") (pintype "passive"))
      (node (ref "R3") (pin "2") (pinfunction "2_2") (pintype "passive"))
      (node (ref "R5") (pin "1") (pinfunction "1_1") (pintype "passive"))
    )
    (net (code "65") (name "Net-(Q1-C)") (class "Default")
      (node (ref "B1") (pin "2") (pinfunction "2_2") (pintype "passive"))
      (node (ref "Q1") (pin "3") (pinfunction "C_3") (pintype "passive"))
    )
    (net (code "66") (name "Net-(Q2-B)") (class "Default")
      (node (ref "Q2") (pin "2") (pinfunction "B_2") (pintype "passive"))
      (node (ref "R6") (pin "2") (pinfunction "2_2") (pintype "passive"))
    )
    (net (code "67") (name "Net-(Q2-C)") (class "Default")
      (node (ref "D1") (pin "2") (pintype "passive"))
      (node (ref "Q2") (pin "3") (pinfunction "C_3") (pintype "passive"))
      (node (ref "R4") (pin "2") (pinfunction "2_2") (pintype "passive"))
    )
    (net (code "68") (name "Net-(Q2-E)") (class "Default")
      (node (ref "Q2") (pin "1") (pinfunction "E_1") (pintype "passive"))
      (node (ref "R8") (pin "1") (pinfunction "1_1") (pintype "passive"))
      (node (ref "U2") (pin "14") (pinfunction "RTS#_14") (pintype "passive"))
    )
    (net (code "69") (name "Net-(Q3-B)") (class "Default")
      (node (ref "Q3") (pin "2") (pinfunction "B_2") (pintype "passive"))
      (node (ref "R8") (pin "2") (pinfunction "2_2") (pintype "passive"))
    )
    (net (code "70") (name "Net-(Q3-C)") (class "Default")
      (node (ref "Q3") (pin "3") (pinfunction "C_3") (pintype "passive"))
      (node (ref "R10") (pin "1") (pinfunction "1_1") (pintype "passive"))
    )
    (net (code "71") (name "Net-(U1-VDDA)") (class "Default")
      (node (ref "C10") (pin "1") (pinfunction "1_1") (pintype "passive"))
      (node (ref "C9") (pin "1") (pinfunction "1_1") (pintype "passive"))
      (node (ref "R12") (pin "1") (pinfunction "1_1") (pintype "passive"))
      (node (ref "U1") (pin "13") (pinfunction "VDDA_13") (pintype "passive"))
    )
    (net (code "72") (name "Net-(U2-DTR#)") (class "Default")
      (node (ref "R6") (pin "1") (pinfunction "1_1") (pintype "passive"))
      (node (ref "U2") (pin "13") (pinfunction "DTR#_13") (pintype "passive"))
    )
    (net (code "73") (name "Net-(U2-V3)") (class "Default")
      (node (ref "C7") (pin "1") (pintype "passive"))
      (node (ref "U2") (pin "4") (pinfunction "V3_4") (pintype "passive"))
    )
    (net (code "74") (name "Net-(U2-XI)") (class "Default")
      (node (ref "C12") (pin "2") (pintype "passive"))
      (node (ref "U2") (pin "7") (pinfunction "XI_7") (pintype "passive"))
      (node (ref "Y3") (pin "1") (pinfunction "OSC1_1") (pintype "passive"))
    )
    (net (code "75") (name "Net-(U2-XO)") (class "Default")
      (node (ref "C11") (pin "2") (pintype "passive"))
      (node (ref "U2") (pin "8") (pinfunction "XO_8") (pintype "passive"))
      (node (ref "Y3") (pin "2") (pinfunction "OSC2_2") (pintype "passive"))
    )
    (net (code "76") (name "Net-(U3-GPIO15)") (class "Default")
      (node (ref "R13") (pin "2") (pinfunction "2_2") (pintype "passive"))
      (node (ref "U3") (pin "16") (pinfunction "GPIO15_16") (pintype "passive"))
    )
    (net (code "77") (name "Net-(U5A-+)") (class "Default")
      (node (ref "R16") (pin "2") (pinfunction "2_2") (pintype "passive"))
      (node (ref "U5") (pin "3") (pinfunction "+_3") (pintype "passive"))
    )
    (net (code "78") (name "Net-(U5A--)") (class "Default")
      (node (ref "R23") (pin "1") (pinfunction "1_1") (pintype "passive"))
      (node (ref "U5") (pin "2") (pinfunction "-_2") (pintype "passive"))
      (node (ref "U6") (pin "3") (pinfunction "D_3") (pintype "passive"))
    )
    (net (code "79") (name "Net-(U5A-out)") (class "Default")
      (node (ref "R20") (pin "1") (pinfunction "1_1") (pintype "passive"))
      (node (ref "R23") (pin "2") (pinfunction "2_2") (pintype "passive"))
      (node (ref "U5") (pin "1") (pinfunction "out_1") (pintype "passive"))
    )
    (net (code "80") (name "Net-(U5B-+)") (class "Default")
      (node (ref "R15") (pin "2") (pinfunction "2_2") (pintype "passive"))
      (node (ref "U5") (pin "5") (pinfunction "+_5") (pintype "passive"))
    )
    (net (code "81") (name "Net-(U5B--)") (class "Default")
      (node (ref "R20") (pin "2") (pinfunction "2_2") (pintype "passive"))
      (node (ref "R22") (pin "1") (pinfunction "1_1") (pintype "passive"))
      (node (ref "U5") (pin "6") (pinfunction "-_6") (pintype "passive"))
    )
    (net (code "82") (name "Net-(U5B-out)") (class "Default")
      (node (ref "R18") (pin "1") (pinfunction "1_1") (pintype "passive"))
      (node (ref "R22") (pin "2") (pinfunction "2_2") (pintype "passive"))
      (node (ref "U5") (pin "7") (pinfunction "out_7") (pintype "passive"))
    )
    (net (code "83") (name "Net-(U7A-+)") (class "Default")
      (node (ref "C18") (pin "2") (pinfunction "2_2") (pintype "passive"))
      (node (ref "R19") (pin "2") (pinfunction "2_2") (pintype "passive"))
      (node (ref "U7") (pin "3") (pinfunction "+_3") (pintype "passive"))
    )
    (net (code "84") (name "Net-(U8-NC)") (class "Default")
      (node (ref "C36") (pin "1") (pintype "passive"))
      (node (ref "U8") (pin "4") (pinfunction "NC_4") (pintype "passive"))
    )
    (net (code "85") (name "USB_VCC") (class "Default")
      (node (ref "R30") (pin "1") (pinfunction "1_1") (pintype "passive"))
      (node (ref "USB_1") (pin "1") (pinfunction "VCC_1") (pintype "passive"))
    )
    (net (code "86") (name "VCC3.3") (class "Default")
      (node (ref "B1") (pin "1") (pinfunction "1_1") (pintype "passive"))
      (node (ref "BOOT1") (pin "1") (pinfunction "1_1") (pintype "passive"))
      (node (ref "BOOT1") (pin "2") (pinfunction "2_2") (pintype "passive"))
      (node (ref "C14") (pin "2") (pinfunction "2_2") (pintype "passive"))
      (node (ref "C15") (pin "2") (pinfunction "2_2") (pintype "passive"))
      (node (ref "C16") (pin "2") (pinfunction "2_2") (pintype "passive"))
      (node (ref "C25") (pin "1") (pintype "passive"))
      (node (ref "C26") (pin "1") (pintype "passive"))
      (node (ref "C27") (pin "1") (pintype "passive"))
      (node (ref "C28") (pin "1") (pintype "passive"))
      (node (ref "C32") (pin "1") (pintype "passive"))
      (node (ref "C33") (pin "1") (pintype "passive"))
      (node (ref "C4") (pin "2") (pinfunction "2_2") (pintype "passive"))
      (node (ref "P1") (pin "2") (pinfunction "2_2") (pintype "passive"))
      (node (ref "Q3") (pin "1") (pinfunction "E_1") (pintype "passive"))
      (node (ref "R11") (pin "2") (pinfunction "2_2") (pintype "passive"))
      (node (ref "R12") (pin "2") (pinfunction "2_2") (pintype "passive"))
      (node (ref "R28") (pin "2") (pinfunction "2_2") (pintype "passive"))
      (node (ref "R4") (pin "1") (pinfunction "1_1") (pintype "passive"))
      (node (ref "R9") (pin "1") (pinfunction "1_1") (pintype "passive"))
      (node (ref "U1") (pin "1") (pinfunction "VBAT_1") (pintype "passive"))
      (node (ref "U1") (pin "19") (pinfunction "VDD_19") (pintype "passive"))
      (node (ref "U1") (pin "32") (pinfunction "VDD_32") (pintype "passive"))
      (node (ref "U1") (pin "48") (pinfunction "VDD_48") (pintype "passive"))
      (node (ref "U1") (pin "64") (pinfunction "VDD_64") (pintype "passive"))
      (node (ref "U3") (pin "3") (pinfunction "CH_PD_3") (pintype "passive"))
      (node (ref "U3") (pin "8") (pinfunction "VCC_8") (pintype "passive"))
      (node (ref "U4") (pin "2") (pinfunction "VCC_2") (pintype "passive"))
      (node (ref "U8") (pin "5") (pinfunction "VOUT_5") (pintype "passive"))
    )
    (net (code "87") (name "VCC5V") (class "Default")
      (node (ref "C29") (pin "1") (pintype "passive"))
      (node (ref "C3") (pin "2") (pintype "passive"))
      (node (ref "C31") (pin "1") (pintype "passive"))
      (node (ref "C6") (pin "2") (pintype "passive"))
      (node (ref "R29") (pin "2") (pinfunction "2_2") (pintype "passive"))
      (node (ref "R30") (pin "2") (pinfunction "2_2") (pintype "passive"))
      (node (ref "U2") (pin "16") (pinfunction "VCC_16") (pintype "passive"))
      (node (ref "U8") (pin "1") (pinfunction "VIN_1") (pintype "passive"))
      (node (ref "U8") (pin "3") (pinfunction "CE_3") (pintype "passive"))
    )
    (net (code "88") (name "VDD") (class "Default")
      (node (ref "C21") (pin "1") (pintype "passive"))
      (node (ref "L1") (pin "2") (pinfunction "2_2") (pintype "passive"))
      (node (ref "R17") (pin "2") (pinfunction "2_2") (pintype "passive"))
      (node (ref "R24") (pin "2") (pinfunction "2_2") (pintype "passive"))
      (node (ref "TC2") (pin "1") (pinfunction "1_1") (pintype "passive"))
      (node (ref "U5") (pin "8") (pinfunction "v+_8") (pintype "passive"))
      (node (ref "U6") (pin "16") (pinfunction "VDD_16") (pintype "passive"))
      (node (ref "U7") (pin "8") (pinfunction "v+_8") (pintype "passive"))
    )
    (net (code "89") (name "VDD5V") (class "Default")
      (node (ref "C22") (pin "1") (pintype "passive"))
      (node (ref "L2") (pin "2") (pinfunction "2_2") (pintype "passive"))
      (node (ref "R25") (pin "2") (pinfunction "2_2") (pintype "passive"))
      (node (ref "R29") (pin "1") (pinfunction "1_1") (pintype "passive"))
      (node (ref "TC3") (pin "1") (pinfunction "1_1") (pintype "passive"))
    )
    (net (code "90") (name "VEE") (class "Default")
      (node (ref "C34") (pin "1") (pintype "passive"))
      (node (ref "C35") (pin "2") (pintype "passive"))
      (node (ref "D8") (pin "1") (pinfunction "A_1") (pintype "passive"))
      (node (ref "IC3") (pin "6") (pinfunction "GND_6") (pintype "passive"))
      (node (ref "R14") (pin "2") (pinfunction "2_2") (pintype "passive"))
      (node (ref "R32") (pin "1") (pinfunction "1_1") (pintype "passive"))
      (node (ref "TC4") (pin "2") (pinfunction "2_2") (pintype "passive"))
      (node (ref "U5") (pin "4") (pinfunction "v-_4") (pintype "passive"))
      (node (ref "U6") (pin "7") (pinfunction "VSS_7") (pintype "passive"))
      (node (ref "U7") (pin "4") (pinfunction "v-_4") (pintype "passive"))
    )
    (net (code "91") (name "unconnected-(IC1-ENA-Pad5)") (class "Default")
      (node (ref "IC1") (pin "5") (pinfunction "ENA_5") (pintype "passive+no_connect"))
    )
    (net (code "92") (name "unconnected-(IC2-ENA-Pad5)") (class "Default")
      (node (ref "IC2") (pin "5") (pinfunction "ENA_5") (pintype "passive+no_connect"))
    )
    (net (code "93") (name "unconnected-(IC3-ENA-Pad5)") (class "Default")
      (node (ref "IC3") (pin "5") (pinfunction "ENA_5") (pintype "passive+no_connect"))
    )
    (net (code "94") (name "unconnected-(JP3-Pad1)") (class "Default")
      (node (ref "JP3") (pin "1") (pinfunction "1_1") (pintype "passive+no_connect"))
    )
    (net (code "95") (name "unconnected-(JP3-Pad4)") (class "Default")
      (node (ref "JP3") (pin "4") (pinfunction "4_4") (pintype "passive+no_connect"))
    )
    (net (code "96") (name "unconnected-(JP3-Pad5)") (class "Default")
      (node (ref "JP3") (pin "5") (pinfunction "5_5") (pintype "passive+no_connect"))
    )
    (net (code "97") (name "unconnected-(JP3-Pad6)") (class "Default")
      (node (ref "JP3") (pin "6") (pinfunction "6_6") (pintype "passive+no_connect"))
    )
    (net (code "98") (name "unconnected-(U1-PA0{slash}WKUP{slash}ADC0{slash}TIM2_CH1_ETR{slash}TIM5_CH1{slash}TIM8_ETR-Pad14)") (class "Default")
      (node (ref "U1") (pin "14") (pinfunction "PA0/WKUP/ADC0/TIM2_CH1_ETR/TIM5_CH1/TIM8_ETR_14") (pintype "passive+no_connect"))
    )
    (net (code "99") (name "unconnected-(U1-PA2{slash}U2_TX{slash}ADC2{slash}TIM2_CH3{slash}TIM5_CH3-Pad16)") (class "Default")
      (node (ref "U1") (pin "16") (pinfunction "PA2/U2_TX/ADC2/TIM2_CH3/TIM5_CH3_16") (pintype "passive+no_connect"))
    )
    (net (code "100") (name "unconnected-(U1-PA3{slash}U2_RX{slash}ADC3{slash}TIM2_CH4{slash}TIM5_CH4-Pad17)") (class "Default")
      (node (ref "U1") (pin "17") (pinfunction "PA3/U2_RX/ADC3/TIM2_CH4/TIM5_CH4_17") (pintype "passive+no_connect"))
    )
    (net (code "101") (name "unconnected-(U1-PA11{slash}CAN_RX{slash}USBDM{slash}TIM1_CH4-Pad44)") (class "Default")
      (node (ref "U1") (pin "44") (pinfunction "PA11/CAN_RX/USBDM/TIM1_CH4_44") (pintype "passive+no_connect"))
    )
    (net (code "102") (name "unconnected-(U1-PA12{slash}CAN_TX{slash}USBDP{slash}TIM1_ETR-Pad45)") (class "Default")
      (node (ref "U1") (pin "45") (pinfunction "PA12/CAN_TX/USBDP/TIM1_ETR_45") (pintype "passive+no_connect"))
    )
    (net (code "103") (name "unconnected-(U1-PA13{slash}JTMS{slash}SWDIO-Pad46)") (class "Default")
      (node (ref "U1") (pin "46") (pinfunction "PA13/JTMS/SWDIO_46") (pintype "passive+no_connect"))
    )
    (net (code "104") (name "unconnected-(U1-PA14{slash}JTCK{slash}SWCLK-Pad49)") (class "Default")
      (node (ref "U1") (pin "49") (pinfunction "PA14/JTCK/SWCLK_49") (pintype "passive+no_connect"))
    )
    (net (code "105") (name "unconnected-(U1-PA15{slash}JTDI{slash}SPI3_NSS{slash}I2S3_WS-Pad50)") (class "Default")
      (node (ref "U1") (pin "50") (pinfunction "PA15/JTDI/SPI3_NSS/I2S3_WS_50") (pintype "passive+no_connect"))
    )
    (net (code "106") (name "unconnected-(U1-PB4{slash}JNTRST{slash}SPI3_MISO-Pad56)") (class "Default")
      (node (ref "U1") (pin "56") (pinfunction "PB4/JNTRST/SPI3_MISO_56") (pintype "passive+no_connect"))
    )
    (net (code "107") (name "unconnected-(U1-PB9{slash}TIM4_CH4{slash}SDIO_D5-Pad62)") (class "Default")
      (node (ref "U1") (pin "62") (pinfunction "PB9/TIM4_CH4/SDIO_D5_62") (pintype "passive+no_connect"))
    )
    (net (code "108") (name "unconnected-(U1-PB14{slash}SPI2_MISO{slash}TIM1_CH2N-Pad35)") (class "Default")
      (node (ref "U1") (pin "35") (pinfunction "PB14/SPI2_MISO/TIM1_CH2N_35") (pintype "passive+no_connect"))
    )
    (net (code "109") (name "unconnected-(U1-PC0{slash}ADC10-Pad8)") (class "Default")
      (node (ref "U1") (pin "8") (pinfunction "PC0/ADC10_8") (pintype "passive+no_connect"))
    )
    (net (code "110") (name "unconnected-(U1-PC1{slash}ADC11-Pad9)") (class "Default")
      (node (ref "U1") (pin "9") (pinfunction "PC1/ADC11_9") (pintype "passive+no_connect"))
    )
    (net (code "111") (name "unconnected-(U1-PC2{slash}ADC12-Pad10)") (class "Default")
      (node (ref "U1") (pin "10") (pinfunction "PC2/ADC12_10") (pintype "passive+no_connect"))
    )
    (net (code "112") (name "unconnected-(U1-PC3{slash}ADC13-Pad11)") (class "Default")
      (node (ref "U1") (pin "11") (pinfunction "PC3/ADC13_11") (pintype "passive+no_connect"))
    )
    (net (code "113") (name "unconnected-(U1-PC4{slash}ADC14-Pad24)") (class "Default")
      (node (ref "U1") (pin "24") (pinfunction "PC4/ADC14_24") (pintype "passive+no_connect"))
    )
    (net (code "114") (name "unconnected-(U1-PC5{slash}ADC15-Pad25)") (class "Default")
      (node (ref "U1") (pin "25") (pinfunction "PC5/ADC15_25") (pintype "passive+no_connect"))
    )
    (net (code "115") (name "unconnected-(U1-PC6{slash}I2S2_MCK{slash}TIM8_CH1{slash}SDIO_D6-Pad37)") (class "Default")
      (node (ref "U1") (pin "37") (pinfunction "PC6/I2S2_MCK/TIM8_CH1/SDIO_D6_37") (pintype "passive+no_connect"))
    )
    (net (code "116") (name "unconnected-(U1-PC7{slash}I2S3_MCK{slash}TIM8_CH2{slash}SDIO_D7-Pad38)") (class "Default")
      (node (ref "U1") (pin "38") (pinfunction "PC7/I2S3_MCK/TIM8_CH2/SDIO_D7_38") (pintype "passive+no_connect"))
    )
    (net (code "117") (name "unconnected-(U1-PC8{slash}TIM8_CH3{slash}SDIO_D0-Pad39)") (class "Default")
      (node (ref "U1") (pin "39") (pinfunction "PC8/TIM8_CH3/SDIO_D0_39") (pintype "passive+no_connect"))
    )
    (net (code "118") (name "unconnected-(U1-PC9{slash}TIM8_CH4{slash}SDIO_D1-Pad40)") (class "Default")
      (node (ref "U1") (pin "40") (pinfunction "PC9/TIM8_CH4/SDIO_D1_40") (pintype "passive+no_connect"))
    )
    (net (code "119") (name "unconnected-(U1-PC10{slash}U4_TX{slash}SDIO_D2-Pad51)") (class "Default")
      (node (ref "U1") (pin "51") (pinfunction "PC10/U4_TX/SDIO_D2_51") (pintype "passive+no_connect"))
    )
    (net (code "120") (name "unconnected-(U1-PC11{slash}U4_RX{slash}SDIO_D3-Pad52)") (class "Default")
      (node (ref "U1") (pin "52") (pinfunction "PC11/U4_RX/SDIO_D3_52") (pintype "passive+no_connect"))
    )
    (net (code "121") (name "unconnected-(U1-PC12{slash}U5_TX{slash}SDIO_CK-Pad53)") (class "Default")
      (node (ref "U1") (pin "53") (pinfunction "PC12/U5_TX/SDIO_CK_53") (pintype "passive+no_connect"))
    )
    (net (code "122") (name "unconnected-(U1-PC13{slash}ANT1-Pad2)") (class "Default")
      (node (ref "U1") (pin "2") (pinfunction "PC13/ANT1_2") (pintype "passive+no_connect"))
    )
    (net (code "123") (name "unconnected-(U2-CTS#-Pad9)") (class "Default")
      (node (ref "U2") (pin "9") (pinfunction "CTS#_9") (pintype "passive+no_connect"))
    )
    (net (code "124") (name "unconnected-(U2-DCD#-Pad12)") (class "Default")
      (node (ref "U2") (pin "12") (pinfunction "DCD#_12") (pintype "passive+no_connect"))
    )
    (net (code "125") (name "unconnected-(U2-DSR#-Pad10)") (class "Default")
      (node (ref "U2") (pin "10") (pinfunction "DSR#_10") (pintype "passive+no_connect"))
    )
    (net (code "126") (name "unconnected-(U2-R232-Pad15)") (class "Default")
      (node (ref "U2") (pin "15") (pinfunction "R232_15") (pintype "passive+no_connect"))
    )
    (net (code "127") (name "unconnected-(U2-RI#-Pad11)") (class "Default")
      (node (ref "U2") (pin "11") (pinfunction "RI#_11") (pintype "passive+no_connect"))
    )
    (net (code "128") (name "unconnected-(U3-ADC-Pad2)") (class "Default")
      (node (ref "U3") (pin "2") (pinfunction "ADC_2") (pintype "passive+no_connect"))
    )
    (net (code "129") (name "unconnected-(U3-CS0-Pad9)") (class "Default")
      (node (ref "U3") (pin "9") (pinfunction "CS0_9") (pintype "passive"))
    )
    (net (code "130") (name "unconnected-(U3-GPIO2-Pad17)") (class "Default")
      (node (ref "U3") (pin "17") (pinfunction "GPIO2_17") (pintype "passive+no_connect"))
    )
    (net (code "131") (name "unconnected-(U3-GPIO4-Pad19)") (class "Default")
      (node (ref "U3") (pin "19") (pinfunction "GPIO4_19") (pintype "passive+no_connect"))
    )
    (net (code "132") (name "unconnected-(U3-GPIO5-Pad20)") (class "Default")
      (node (ref "U3") (pin "20") (pinfunction "GPIO5_20") (pintype "passive+no_connect"))
    )
    (net (code "133") (name "unconnected-(U3-GPIO9-Pad11)") (class "Default")
      (node (ref "U3") (pin "11") (pinfunction "GPIO9_11") (pintype "passive"))
    )
    (net (code "134") (name "unconnected-(U3-GPIO10-Pad12)") (class "Default")
      (node (ref "U3") (pin "12") (pinfunction "GPIO10_12") (pintype "passive"))
    )
    (net (code "135") (name "unconnected-(U3-GPIO12-Pad6)") (class "Default")
      (node (ref "U3") (pin "6") (pinfunction "GPIO12_6") (pintype "passive+no_connect"))
    )
    (net (code "136") (name "unconnected-(U3-GPIO13-Pad7)") (class "Default")
      (node (ref "U3") (pin "7") (pinfunction "GPIO13_7") (pintype "passive+no_connect"))
    )
    (net (code "137") (name "unconnected-(U3-GPIO14-Pad5)") (class "Default")
      (node (ref "U3") (pin "5") (pinfunction "GPIO14_5") (pintype "passive+no_connect"))
    )
    (net (code "138") (name "unconnected-(U3-GPIO16-Pad4)") (class "Default")
      (node (ref "U3") (pin "4") (pinfunction "GPIO16_4") (pintype "passive+no_connect"))
    )
    (net (code "139") (name "unconnected-(U3-MISO-Pad10)") (class "Default")
      (node (ref "U3") (pin "10") (pinfunction "MISO_10") (pintype "passive"))
    )
    (net (code "140") (name "unconnected-(U3-MOSI-Pad13)") (class "Default")
      (node (ref "U3") (pin "13") (pinfunction "MOSI_13") (pintype "passive"))
    )
    (net (code "141") (name "unconnected-(U3-SCLK-Pad14)") (class "Default")
      (node (ref "U3") (pin "14") (pinfunction "SCLK_14") (pintype "passive"))
    )
    (net (code "142") (name "unconnected-(U7B-+-Pad5)") (class "Default")
      (node (ref "U7") (pin "5") (pinfunction "+_5") (pintype "passive+no_connect"))
    )
    (net (code "143") (name "unconnected-(U7B---Pad6)") (class "Default")
      (node (ref "U7") (pin "6") (pinfunction "-_6") (pintype "passive+no_connect"))
    )
    (net (code "144") (name "unconnected-(U7B-out-Pad7)") (class "Default")
      (node (ref "U7") (pin "7") (pinfunction "out_7") (pintype "passive+no_connect"))
    )
    (net (code "145") (name "unconnected-(USB_1-NC-Pad4)") (class "Default")
      (node (ref "USB_1") (pin "4") (pinfunction "NC_4") (pintype "passive+no_connect"))
    )
  )
)
